# 2019_FDP_SCHEMA.net
KiCad netlist of a schematic drawn in Altium Designer
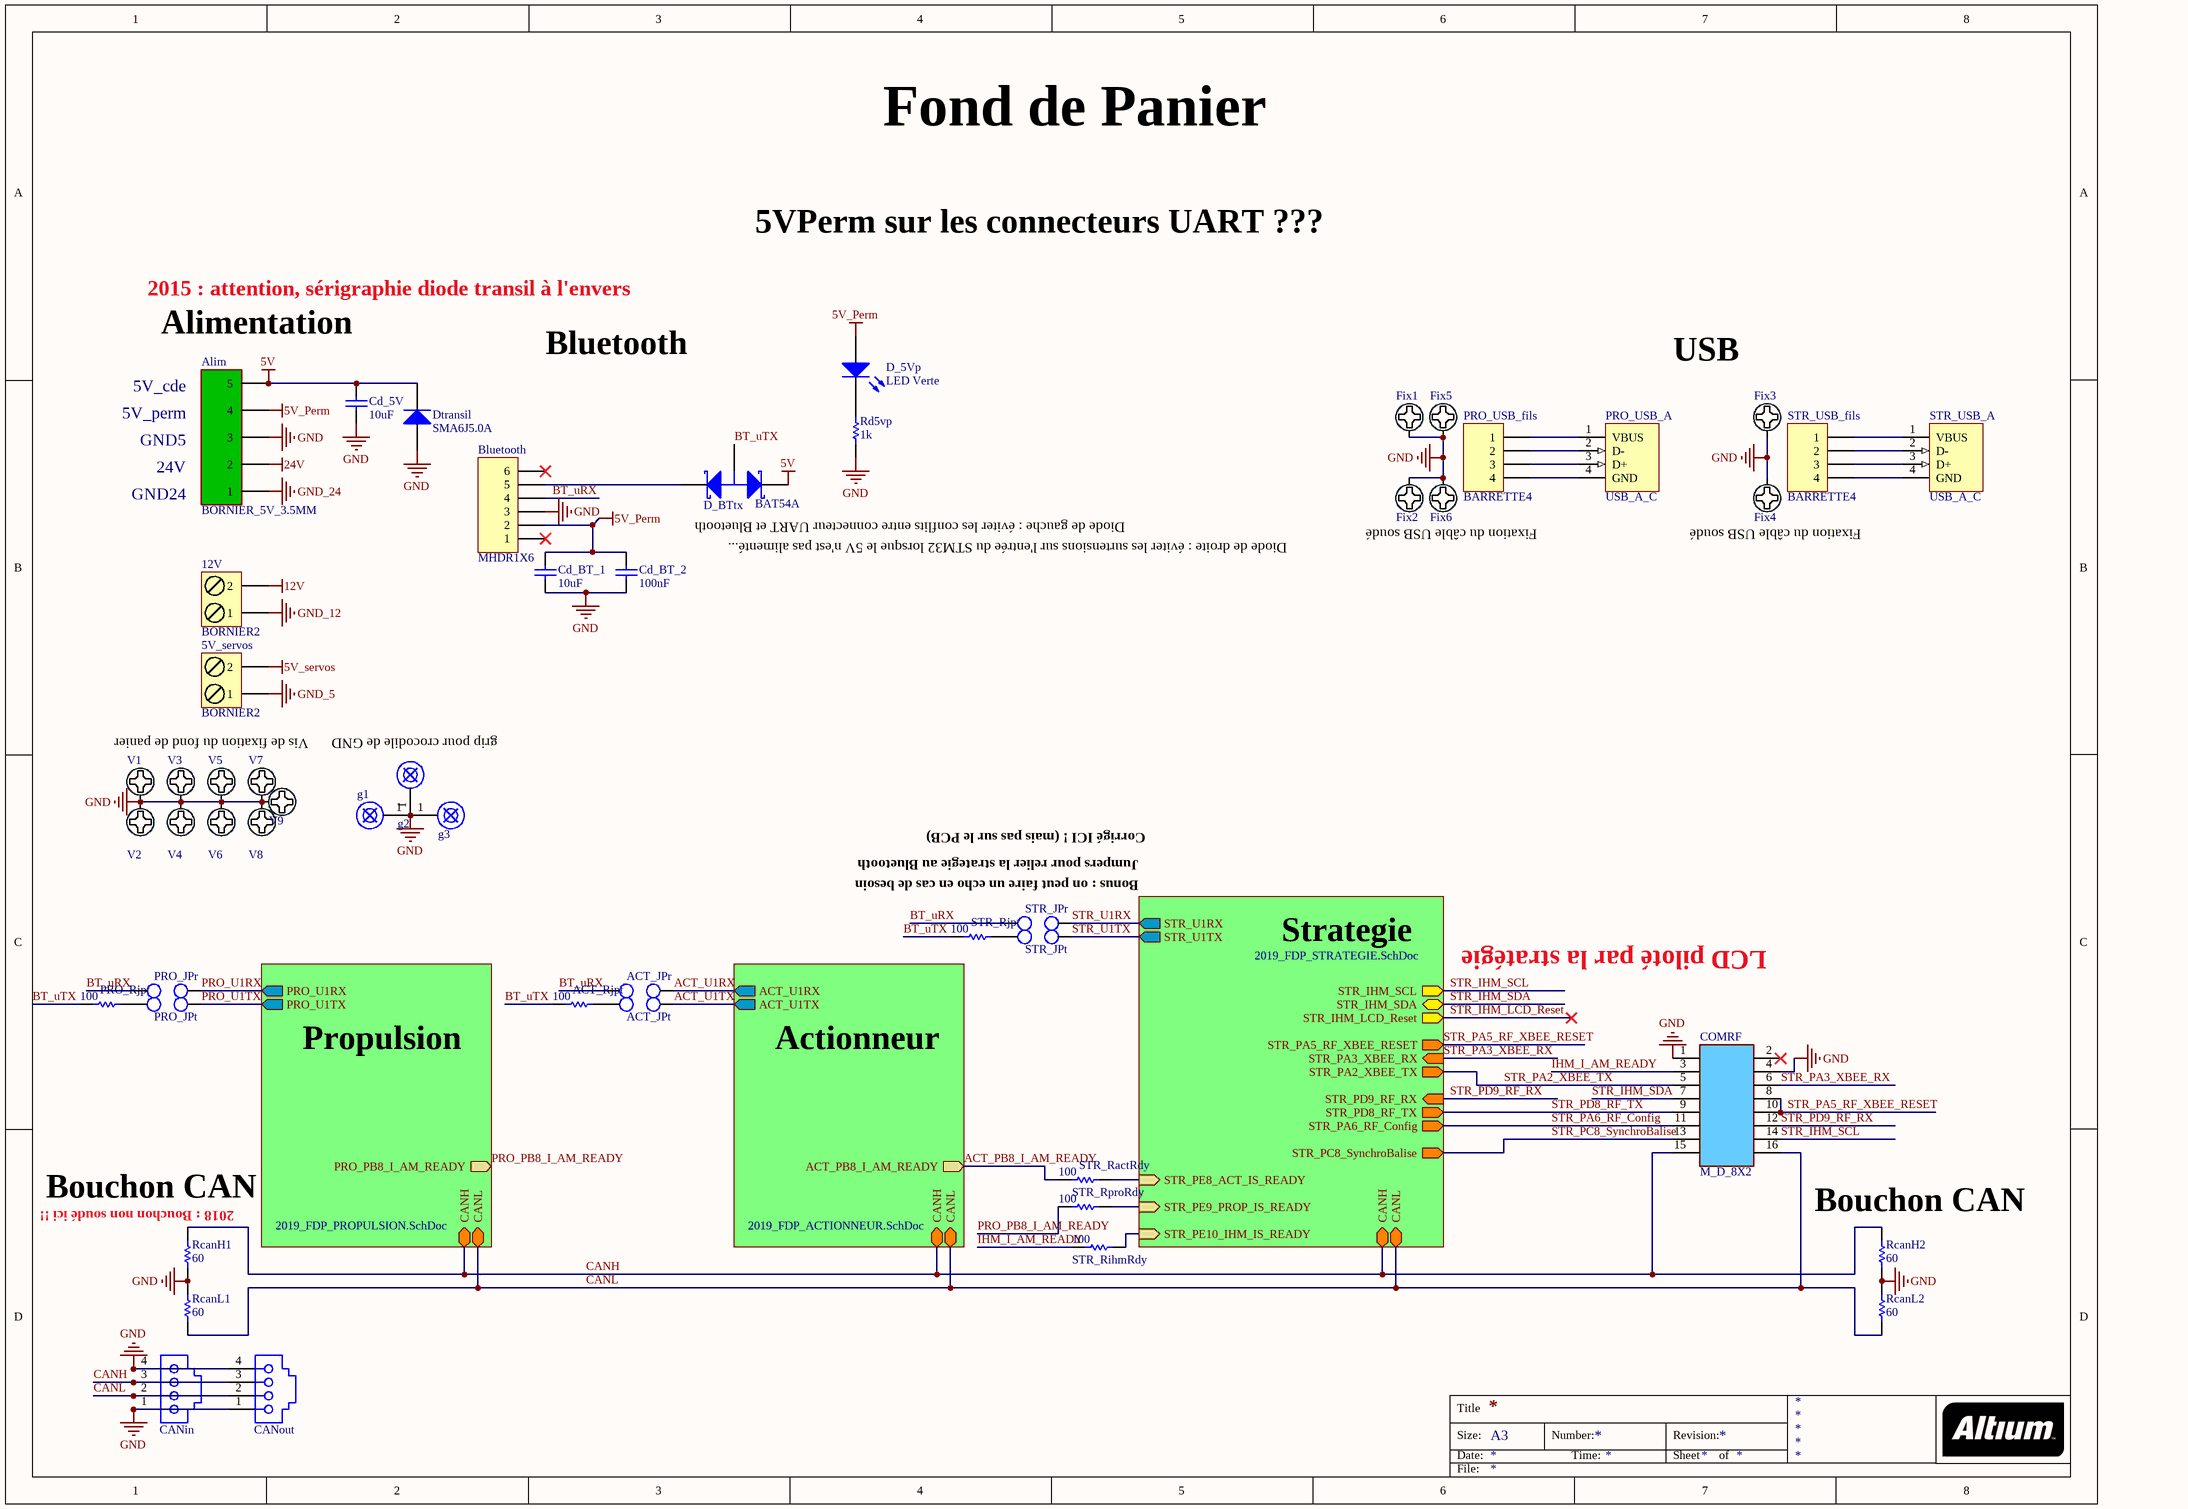
[diagram p0: 2019_FDP_SCHEMA.SchDoc]

(export (version "E")
  (design (tool "Eeschema 10.0.6"))
  (components
    (comp (ref "5V_servos")
      (value "BORNIER2")
      (footprint "BORNIER_2V_5.08MM")
      (description "Terminal blocks, 2 pins, pitch=5mm")
      (libsource (lib "Connecteur") (part "BORNIER2"))
    )
    (comp (ref "12V")
      (value "BORNIER2")
      (footprint "BORNIER_2V_5.08MM")
      (description "Terminal blocks, 2 pins, pitch=5mm")
      (libsource (lib "Connecteur") (part "BORNIER2"))
    )
    (comp (ref "ACT_JPr")
      (value "JUMPER2")
      (footprint "BARRETTE_2_M_D")
      (description "BARRETTE 2 CONTACTS 1 RANGEE MALE DROITE")
      (libsource (lib "connecteurs") (part "JUMPER2"))
    )
    (comp (ref "ACT_JPt")
      (value "JUMPER2")
      (footprint "BARRETTE_2_M_D")
      (description "BARRETTE 2 CONTACTS 1 RANGEE MALE DROITE")
      (libsource (lib "connecteurs") (part "JUMPER2"))
    )
    (comp (ref "ACT_Rjpt")
      (value "100")
      (footprint "R1206_N")
      (description "Resistor")
      (fields (field (name "PUBLISHER") "Altium Limited"))
      (libsource (lib "_ROBOT") (part "Resistor"))
    )
    (comp (ref "Alim")
      (value "BORNIER_5V_3.5MM")
      (footprint "BORNIER_5V_3.5MM_femelle_0")
      (libsource (lib "Connecteur") (part "BORNIER_5V_3.5MM"))
    )
    (comp (ref "Bluetooth")
      (value "MHDR1X6")
      (footprint "HE14_6")
      (description "Header, 6-Pin")
      (fields (field (name "PUBLISHER") "Altium Limited"))
      (libsource (lib "Miscellaneous Connectors") (part "MHDR1X6"))
    )
    (comp (ref "CANin")
      (value "634104149621")
      (footprint "634104149621")
      (description "Modular Jack SMT Vertical Plastic 4P4C Top Entry WR-MJ")
      (fields (field (name "PUBLISHER") "Wurth Elektronik"))
      (libsource (lib "ALTIUM-MJ_VERTICAL_PLASTIC") (part "634104149621"))
    )
    (comp (ref "CANout")
      (value "634104149621")
      (footprint "634104149621")
      (description "Modular Jack SMT Vertical Plastic 4P4C Top Entry WR-MJ")
      (fields (field (name "PUBLISHER") "Wurth Elektronik"))
      (libsource (lib "ALTIUM-MJ_VERTICAL_PLASTIC") (part "634104149621"))
    )
    (comp (ref "Cd_5V")
      (value "10uF")
      (footprint "C1206_N")
      (description "Capacitor")
      (fields (field (name "PUBLISHER") "Altium Limited"))
      (libsource (lib "_ROBOT") (part "Condensateur"))
    )
    (comp (ref "Cd_BT_1")
      (value "10uF")
      (footprint "C1206_N")
      (description "Capacitor")
      (fields (field (name "PUBLISHER") "Altium Limited"))
      (libsource (lib "_ROBOT") (part "Condensateur"))
    )
    (comp (ref "Cd_BT_2")
      (value "100nF")
      (footprint "C0805_N")
      (description "Capacitor")
      (fields (field (name "PUBLISHER") "Altium Limited"))
      (libsource (lib "_ROBOT") (part "Condensateur"))
    )
    (comp (ref "COMRF")
      (value "BARRETTE_8 CONTACTS_2 RANGEES_MALE_DROITE")
      (footprint "HE10/16_M_D_B P")
      (fields (field (name "TYPE") "M_D_8X2"))
      (libsource (lib "connecteurs") (part "BARRETTE_8 CONTACTS_2 RANGEES_MALE_DROITE"))
    )
    (comp (ref "Dtransil")
      (value "SMA6J5.0A")
      (footprint "DO214AC")
      (description "1 Amp General Purpose Rectifier")
      (fields (field (name "PUBLISHER") "Altium Limited"))
      (libsource (lib "Miscellaneous Devices") (part "Diode 1N4001"))
    )
    (comp (ref "D_5Vp")
      (value "LED Verte")
      (footprint "LED_0805")
      (description "Typical LED")
      (fields (field (name "PUBLISHER") "Altium Limited"))
      (libsource (lib "_ROBOT") (part "LED"))
    )
    (comp (ref "D_BTtx")
      (value "BAT54A")
      (footprint "SOT23-3N")
      (description "DIODE SCHOTTKY DOUBLE")
      (fields (field (name "MANUFACTURER") "ZETEX"))
      (libsource (lib "_ROBOT") (part "Diode Shottky double  BAT54A"))
    )
    (comp (ref "Fix1")
      (value "Pad_M3")
      (footprint "Point Test_D3_P1.6mm")
      (description "Vis M3 X 6mm _TORX_Tête 6mm")
      (fields (field (name "PUBLISHER") "Damien Guitton"))
      (libsource (lib "DG_Mecanique") (part "Vis M3 X 6mm _TORX_Tête 6mm"))
    )
    (comp (ref "Fix2")
      (value "Pad_M3")
      (footprint "Point Test_D3_P1.6mm")
      (description "Vis M3 X 6mm _TORX_Tête 6mm")
      (fields (field (name "PUBLISHER") "Damien Guitton"))
      (libsource (lib "DG_Mecanique") (part "Vis M3 X 6mm _TORX_Tête 6mm"))
    )
    (comp (ref "Fix3")
      (value "Pad_M3")
      (footprint "Point Test_D3_P1.6mm")
      (description "Vis M3 X 6mm _TORX_Tête 6mm")
      (fields (field (name "PUBLISHER") "Damien Guitton"))
      (libsource (lib "DG_Mecanique") (part "Vis M3 X 6mm _TORX_Tête 6mm"))
    )
    (comp (ref "Fix4")
      (value "Pad_M3")
      (footprint "Point Test_D3_P1.6mm")
      (description "Vis M3 X 6mm _TORX_Tête 6mm")
      (fields (field (name "PUBLISHER") "Damien Guitton"))
      (libsource (lib "DG_Mecanique") (part "Vis M3 X 6mm _TORX_Tête 6mm"))
    )
    (comp (ref "Fix5")
      (value "Pad_M3")
      (footprint "Point Test_D3_P1.6mm")
      (description "Vis M3 X 6mm _TORX_Tête 6mm")
      (fields (field (name "PUBLISHER") "Damien Guitton"))
      (libsource (lib "DG_Mecanique") (part "Vis M3 X 6mm _TORX_Tête 6mm"))
    )
    (comp (ref "Fix6")
      (value "Pad_M3")
      (footprint "Point Test_D3_P1.6mm")
      (description "Vis M3 X 6mm _TORX_Tête 6mm")
      (fields (field (name "PUBLISHER") "Damien Guitton"))
      (libsource (lib "DG_Mecanique") (part "Vis M3 X 6mm _TORX_Tête 6mm"))
    )
    (comp (ref "g1")
      (value "grip")
      (footprint "POINT_TEST")
      (description "POINT TEST")
      (libsource (lib "connecteurs") (part "POINT_TEST"))
    )
    (comp (ref "g2")
      (value "grip")
      (footprint "POINT_TEST")
      (description "POINT TEST")
      (libsource (lib "connecteurs") (part "POINT_TEST"))
    )
    (comp (ref "g3")
      (value "grip")
      (footprint "POINT_TEST")
      (description "POINT TEST")
      (libsource (lib "connecteurs") (part "POINT_TEST"))
    )
    (comp (ref "PRO_JPr")
      (value "JUMPER2")
      (footprint "BARRETTE_2_M_D")
      (description "BARRETTE 2 CONTACTS 1 RANGEE MALE DROITE")
      (libsource (lib "connecteurs") (part "JUMPER2"))
    )
    (comp (ref "PRO_JPt")
      (value "JUMPER2")
      (footprint "BARRETTE_2_M_D")
      (description "BARRETTE 2 CONTACTS 1 RANGEE MALE DROITE")
      (libsource (lib "connecteurs") (part "JUMPER2"))
    )
    (comp (ref "PRO_Rjpt")
      (value "100")
      (footprint "R1206_N")
      (description "Resistor")
      (fields (field (name "PUBLISHER") "Altium Limited"))
      (libsource (lib "_ROBOT") (part "Resistor"))
    )
    (comp (ref "PRO_USB_A")
      (value "USB_A_COUDEE")
      (footprint "USB_A_C")
      (description "EMBASE USB TRAVERSANTE TYPE A COUDEE")
      (fields (field (name "TYPE") "USB_A_C"))
      (libsource (lib "connecteurs") (part "USB_A_COUDEE"))
    )
    (comp (ref "PRO_USB_fils")
      (value "BARRETTE4")
      (footprint "HE14_4")
      (description "Header, 4-Pin")
      (fields (field (name "PUBLISHER") "Altium Limited"))
      (libsource (lib "Connecteur") (part "BARRETTE4"))
    )
    (comp (ref "RcanH1")
      (value "60")
      (footprint "R1206_N")
      (description "Resistor")
      (fields (field (name "PUBLISHER") "Altium Limited"))
      (libsource (lib "_ROBOT") (part "Resistor"))
    )
    (comp (ref "RcanH2")
      (value "60")
      (footprint "R1206_N")
      (description "Resistor")
      (fields (field (name "PUBLISHER") "Altium Limited"))
      (libsource (lib "_ROBOT") (part "Resistor"))
    )
    (comp (ref "RcanL1")
      (value "60")
      (footprint "R1206_N")
      (description "Resistor")
      (fields (field (name "PUBLISHER") "Altium Limited"))
      (libsource (lib "_ROBOT") (part "Resistor"))
    )
    (comp (ref "RcanL2")
      (value "60")
      (footprint "R1206_N")
      (description "Resistor")
      (fields (field (name "PUBLISHER") "Altium Limited"))
      (libsource (lib "_ROBOT") (part "Resistor"))
    )
    (comp (ref "Rd5vp")
      (value "1k")
      (footprint "R1206_N")
      (description "Resistor")
      (fields (field (name "PUBLISHER") "Altium Limited"))
      (libsource (lib "_ROBOT") (part "Resistor"))
    )
    (comp (ref "STR_JPr")
      (value "JUMPER2")
      (footprint "BARRETTE_2_M_D")
      (description "BARRETTE 2 CONTACTS 1 RANGEE MALE DROITE")
      (libsource (lib "connecteurs") (part "JUMPER2"))
    )
    (comp (ref "STR_JPt")
      (value "JUMPER2")
      (footprint "BARRETTE_2_M_D")
      (description "BARRETTE 2 CONTACTS 1 RANGEE MALE DROITE")
      (libsource (lib "connecteurs") (part "JUMPER2"))
    )
    (comp (ref "STR_RactRdy")
      (value "100")
      (footprint "R1206_N")
      (description "Resistor")
      (fields (field (name "PUBLISHER") "Altium Limited"))
      (libsource (lib "_ROBOT") (part "Resistor"))
    )
    (comp (ref "STR_RihmRdy")
      (value "100")
      (footprint "R1206_N")
      (description "Resistor")
      (fields (field (name "PUBLISHER") "Altium Limited"))
      (libsource (lib "_ROBOT") (part "Resistor"))
    )
    (comp (ref "STR_Rjpt")
      (value "100")
      (footprint "R1206_N")
      (description "Resistor")
      (fields (field (name "PUBLISHER") "Altium Limited"))
      (libsource (lib "_ROBOT") (part "Resistor"))
    )
    (comp (ref "STR_RproRdy")
      (value "100")
      (footprint "R1206_N")
      (description "Resistor")
      (fields (field (name "PUBLISHER") "Altium Limited"))
      (libsource (lib "_ROBOT") (part "Resistor"))
    )
    (comp (ref "STR_USB_A")
      (value "USB_A_COUDEE")
      (footprint "USB_A_C")
      (description "EMBASE USB TRAVERSANTE TYPE A COUDEE")
      (fields (field (name "TYPE") "USB_A_C"))
      (libsource (lib "connecteurs") (part "USB_A_COUDEE"))
    )
    (comp (ref "STR_USB_fils")
      (value "BARRETTE4")
      (footprint "HE14_4")
      (description "Header, 4-Pin")
      (fields (field (name "PUBLISHER") "Altium Limited"))
      (libsource (lib "Connecteur") (part "BARRETTE4"))
    )
    (comp (ref "V1")
      (value "Pad_M3")
      (footprint "M3x6mm Torx")
      (description "Vis M3 X 6mm _TORX_Tête 6mm")
      (fields (field (name "PUBLISHER") "Damien Guitton"))
      (libsource (lib "DG_Mecanique") (part "Vis M3 X 6mm _TORX_Tête 6mm"))
    )
    (comp (ref "V2")
      (value "Pad_M3")
      (footprint "M3x6mm Torx")
      (description "Vis M3 X 6mm _TORX_Tête 6mm")
      (fields (field (name "PUBLISHER") "Damien Guitton"))
      (libsource (lib "DG_Mecanique") (part "Vis M3 X 6mm _TORX_Tête 6mm"))
    )
    (comp (ref "V3")
      (value "Pad_M3")
      (footprint "M3x6mm Torx")
      (description "Vis M3 X 6mm _TORX_Tête 6mm")
      (fields (field (name "PUBLISHER") "Damien Guitton"))
      (libsource (lib "DG_Mecanique") (part "Vis M3 X 6mm _TORX_Tête 6mm"))
    )
    (comp (ref "V4")
      (value "Pad_M3")
      (footprint "M3x6mm Torx")
      (description "Vis M3 X 6mm _TORX_Tête 6mm")
      (fields (field (name "PUBLISHER") "Damien Guitton"))
      (libsource (lib "DG_Mecanique") (part "Vis M3 X 6mm _TORX_Tête 6mm"))
    )
    (comp (ref "V5")
      (value "Pad_M3")
      (footprint "M3x6mm Torx")
      (description "Vis M3 X 6mm _TORX_Tête 6mm")
      (fields (field (name "PUBLISHER") "Damien Guitton"))
      (libsource (lib "DG_Mecanique") (part "Vis M3 X 6mm _TORX_Tête 6mm"))
    )
    (comp (ref "V6")
      (value "Pad_M3")
      (footprint "M3x6mm Torx")
      (description "Vis M3 X 6mm _TORX_Tête 6mm")
      (fields (field (name "PUBLISHER") "Damien Guitton"))
      (libsource (lib "DG_Mecanique") (part "Vis M3 X 6mm _TORX_Tête 6mm"))
    )
    (comp (ref "V7")
      (value "Pad_M3")
      (footprint "M3x6mm Torx")
      (description "Vis M3 X 6mm _TORX_Tête 6mm")
      (fields (field (name "PUBLISHER") "Damien Guitton"))
      (libsource (lib "DG_Mecanique") (part "Vis M3 X 6mm _TORX_Tête 6mm"))
    )
    (comp (ref "V8")
      (value "Pad_M3")
      (footprint "M3x6mm Torx")
      (description "Vis M3 X 6mm _TORX_Tête 6mm")
      (fields (field (name "PUBLISHER") "Damien Guitton"))
      (libsource (lib "DG_Mecanique") (part "Vis M3 X 6mm _TORX_Tête 6mm"))
    )
    (comp (ref "V9")
      (value "Pad_M3")
      (footprint "M3x6mm Torx")
      (description "Vis M3 X 6mm _TORX_Tête 6mm")
      (fields (field (name "PUBLISHER") "Damien Guitton"))
      (libsource (lib "DG_Mecanique") (part "Vis M3 X 6mm _TORX_Tête 6mm"))
    )
  )
  (nets
    (net (code "1") (name "/ACT_PB8_I_AM_READY") (class "Default")
      (node (ref "STR_RactRdy") (pin "2") (pinfunction "2_2") (pintype "passive"))
    )
    (net (code "2") (name "/ACT_U1RX") (class "Default")
      (node (ref "ACT_JPr") (pin "2") (pinfunction "2_2") (pintype "passive"))
    )
    (net (code "3") (name "/ACT_U1TX") (class "Default")
      (node (ref "ACT_JPt") (pin "2") (pinfunction "2_2") (pintype "passive"))
    )
    (net (code "4") (name "/BT_uRX") (class "Default")
      (node (ref "ACT_JPr") (pin "1") (pinfunction "1_1") (pintype "passive"))
      (node (ref "Bluetooth") (pin "4") (pinfunction "4_4") (pintype "passive"))
      (node (ref "PRO_JPr") (pin "1") (pinfunction "1_1") (pintype "passive"))
      (node (ref "STR_JPr") (pin "1") (pinfunction "1_1") (pintype "passive"))
    )
    (net (code "5") (name "/BT_uTX") (class "Default")
      (node (ref "ACT_Rjpt") (pin "2") (pinfunction "2_2") (pintype "passive"))
      (node (ref "D_BTtx") (pin "3") (pinfunction "A_3") (pintype "passive"))
      (node (ref "PRO_Rjpt") (pin "2") (pinfunction "2_2") (pintype "passive"))
      (node (ref "STR_Rjpt") (pin "2") (pinfunction "2_2") (pintype "passive"))
    )
    (net (code "6") (name "/CANH") (class "Default")
      (node (ref "CANin") (pin "3") (pinfunction "3_3") (pintype "passive"))
      (node (ref "CANout") (pin "3") (pinfunction "3_3") (pintype "passive"))
      (node (ref "COMRF") (pin "15") (pinfunction "15_15") (pintype "passive"))
      (node (ref "RcanH1") (pin "2") (pinfunction "2_2") (pintype "passive"))
      (node (ref "RcanH2") (pin "1") (pinfunction "1_1") (pintype "passive"))
    )
    (net (code "7") (name "/CANL") (class "Default")
      (node (ref "CANin") (pin "2") (pinfunction "2_2") (pintype "passive"))
      (node (ref "CANout") (pin "2") (pinfunction "2_2") (pintype "passive"))
      (node (ref "COMRF") (pin "16") (pinfunction "16_16") (pintype "passive"))
      (node (ref "RcanL1") (pin "1") (pinfunction "1_1") (pintype "passive"))
      (node (ref "RcanL2") (pin "1") (pinfunction "1_1") (pintype "passive"))
    )
    (net (code "8") (name "/IHM_I_AM_READY") (class "Default")
      (node (ref "COMRF") (pin "3") (pinfunction "3_3") (pintype "passive"))
      (node (ref "STR_RihmRdy") (pin "2") (pinfunction "2_2") (pintype "passive"))
    )
    (net (code "9") (name "/PRO_PB8_I_AM_READY") (class "Default")
      (node (ref "STR_RproRdy") (pin "2") (pinfunction "2_2") (pintype "passive"))
    )
    (net (code "10") (name "/PRO_U1RX") (class "Default")
      (node (ref "PRO_JPr") (pin "2") (pinfunction "2_2") (pintype "passive"))
    )
    (net (code "11") (name "/PRO_U1TX") (class "Default")
      (node (ref "PRO_JPt") (pin "2") (pinfunction "2_2") (pintype "passive"))
    )
    (net (code "13") (name "/STR_IHM_SCL") (class "Default")
      (node (ref "COMRF") (pin "14") (pinfunction "14_14") (pintype "passive"))
    )
    (net (code "14") (name "/STR_IHM_SDA") (class "Default")
      (node (ref "COMRF") (pin "7") (pinfunction "7_7") (pintype "passive"))
    )
    (net (code "15") (name "/STR_PA2_XBEE_TX") (class "Default")
      (node (ref "COMRF") (pin "5") (pinfunction "5_5") (pintype "passive"))
    )
    (net (code "16") (name "/STR_PA3_XBEE_RX") (class "Default")
      (node (ref "COMRF") (pin "6") (pinfunction "6_6") (pintype "passive"))
    )
    (net (code "17") (name "/STR_PA5_RF_XBEE_RESET") (class "Default")
      (node (ref "COMRF") (pin "10") (pinfunction "10_10") (pintype "passive"))
      (node (ref "COMRF") (pin "8") (pinfunction "8_8") (pintype "passive"))
    )
    (net (code "18") (name "/STR_PA6_RF_Config") (class "Default")
      (node (ref "COMRF") (pin "11") (pinfunction "11_11") (pintype "passive"))
    )
    (net (code "19") (name "/STR_PC8_SynchroBalise") (class "Default")
      (node (ref "COMRF") (pin "13") (pinfunction "13_13") (pintype "passive"))
    )
    (net (code "20") (name "/STR_PD8_RF_TX") (class "Default")
      (node (ref "COMRF") (pin "9") (pinfunction "9_9") (pintype "passive"))
    )
    (net (code "21") (name "/STR_PD9_RF_RX") (class "Default")
      (node (ref "COMRF") (pin "12") (pinfunction "12_12") (pintype "passive"))
    )
    (net (code "22") (name "/STR_PE8_ACT_IS_READY") (class "Default")
      (node (ref "STR_RactRdy") (pin "1") (pinfunction "1_1") (pintype "passive"))
    )
    (net (code "23") (name "/STR_PE9_PROP_IS_READY") (class "Default")
      (node (ref "STR_RproRdy") (pin "1") (pinfunction "1_1") (pintype "passive"))
    )
    (net (code "24") (name "/STR_PE10_IHM_IS_READY") (class "Default")
      (node (ref "STR_RihmRdy") (pin "1") (pinfunction "1_1") (pintype "passive"))
    )
    (net (code "25") (name "/STR_U1RX") (class "Default")
      (node (ref "STR_JPr") (pin "2") (pinfunction "2_2") (pintype "passive"))
    )
    (net (code "26") (name "/STR_U1TX") (class "Default")
      (node (ref "STR_JPt") (pin "2") (pinfunction "2_2") (pintype "passive"))
    )
    (net (code "27") (name "5V") (class "Default")
      (node (ref "Alim") (pin "5") (pinfunction "5_5") (pintype "passive"))
      (node (ref "Cd_5V") (pin "2") (pinfunction "2_2") (pintype "passive"))
      (node (ref "D_BTtx") (pin "2") (pinfunction "K2_2") (pintype "passive"))
      (node (ref "Dtransil") (pin "2") (pinfunction "K_2") (pintype "passive"))
    )
    (net (code "28") (name "5V_Perm") (class "Default")
      (node (ref "Alim") (pin "4") (pinfunction "4_4") (pintype "passive"))
      (node (ref "Bluetooth") (pin "2") (pinfunction "2_2") (pintype "passive"))
      (node (ref "Cd_BT_1") (pin "2") (pinfunction "2_2") (pintype "passive"))
      (node (ref "Cd_BT_2") (pin "2") (pinfunction "2_2") (pintype "passive"))
      (node (ref "D_5Vp") (pin "1") (pinfunction "A_1") (pintype "passive"))
    )
    (net (code "29") (name "5V_servos") (class "Default")
      (node (ref "5V_servos") (pin "2") (pinfunction "2_2") (pintype "passive"))
    )
    (net (code "30") (name "12V") (class "Default")
      (node (ref "12V") (pin "2") (pinfunction "2_2") (pintype "passive"))
    )
    (net (code "31") (name "24V") (class "Default")
      (node (ref "Alim") (pin "2") (pinfunction "2_2") (pintype "passive"))
    )
    (net (code "32") (name "GND") (class "Default")
      (node (ref "Alim") (pin "3") (pinfunction "3_3") (pintype "passive"))
      (node (ref "Bluetooth") (pin "3") (pinfunction "3_3") (pintype "passive"))
      (node (ref "CANin") (pin "1") (pinfunction "1_1") (pintype "passive"))
      (node (ref "CANin") (pin "4") (pinfunction "4_4") (pintype "passive"))
      (node (ref "CANout") (pin "1") (pinfunction "1_1") (pintype "passive"))
      (node (ref "CANout") (pin "4") (pinfunction "4_4") (pintype "passive"))
      (node (ref "COMRF") (pin "1") (pinfunction "1_1") (pintype "passive"))
      (node (ref "COMRF") (pin "4") (pinfunction "4_4") (pintype "passive"))
      (node (ref "Cd_5V") (pin "1") (pinfunction "1_1") (pintype "passive"))
      (node (ref "Cd_BT_1") (pin "1") (pinfunction "1_1") (pintype "passive"))
      (node (ref "Cd_BT_2") (pin "1") (pinfunction "1_1") (pintype "passive"))
      (node (ref "Dtransil") (pin "1") (pinfunction "A_1") (pintype "passive"))
      (node (ref "Fix1") (pin "1") (pinfunction "1_1") (pintype "passive"))
      (node (ref "Fix2") (pin "1") (pinfunction "1_1") (pintype "passive"))
      (node (ref "Fix3") (pin "1") (pinfunction "1_1") (pintype "passive"))
      (node (ref "Fix4") (pin "1") (pinfunction "1_1") (pintype "passive"))
      (node (ref "Fix5") (pin "1") (pinfunction "1_1") (pintype "passive"))
      (node (ref "Fix6") (pin "1") (pinfunction "1_1") (pintype "passive"))
      (node (ref "RcanH1") (pin "1") (pinfunction "1_1") (pintype "passive"))
      (node (ref "RcanH2") (pin "2") (pinfunction "2_2") (pintype "passive"))
      (node (ref "RcanL1") (pin "2") (pinfunction "2_2") (pintype "passive"))
      (node (ref "RcanL2") (pin "2") (pinfunction "2_2") (pintype "passive"))
      (node (ref "Rd5vp") (pin "2") (pinfunction "2_2") (pintype "passive"))
      (node (ref "V1") (pin "1") (pinfunction "1_1") (pintype "passive"))
      (node (ref "V2") (pin "1") (pinfunction "1_1") (pintype "passive"))
      (node (ref "V3") (pin "1") (pinfunction "1_1") (pintype "passive"))
      (node (ref "V4") (pin "1") (pinfunction "1_1") (pintype "passive"))
      (node (ref "V5") (pin "1") (pinfunction "1_1") (pintype "passive"))
      (node (ref "V6") (pin "1") (pinfunction "1_1") (pintype "passive"))
      (node (ref "V7") (pin "1") (pinfunction "1_1") (pintype "passive"))
      (node (ref "V8") (pin "1") (pinfunction "1_1") (pintype "passive"))
      (node (ref "V9") (pin "1") (pinfunction "1_1") (pintype "passive"))
      (node (ref "g1") (pin "1") (pinfunction "3_1") (pintype "passive"))
      (node (ref "g2") (pin "1") (pinfunction "3_1") (pintype "passive"))
      (node (ref "g3") (pin "1") (pinfunction "3_1") (pintype "passive"))
    )
    (net (code "33") (name "GND_5") (class "Default")
      (node (ref "5V_servos") (pin "1") (pinfunction "1_1") (pintype "passive"))
    )
    (net (code "34") (name "GND_12") (class "Default")
      (node (ref "12V") (pin "1") (pinfunction "1_1") (pintype "passive"))
    )
    (net (code "35") (name "GND_24") (class "Default")
      (node (ref "Alim") (pin "1") (pinfunction "1_1") (pintype "passive"))
    )
    (net (code "36") (name "Net-(ACT_JPt-Pad1)") (class "Default")
      (node (ref "ACT_JPt") (pin "1") (pinfunction "1_1") (pintype "passive"))
      (node (ref "ACT_Rjpt") (pin "1") (pinfunction "1_1") (pintype "passive"))
    )
    (net (code "37") (name "Net-(D_5Vp-K)") (class "Default")
      (node (ref "D_5Vp") (pin "2") (pinfunction "K_2") (pintype "passive"))
      (node (ref "Rd5vp") (pin "1") (pinfunction "1_1") (pintype "passive"))
    )
    (net (code "38") (name "Net-(D_BTtx-K1)") (class "Default")
      (node (ref "Bluetooth") (pin "5") (pinfunction "5_5") (pintype "passive"))
      (node (ref "D_BTtx") (pin "1") (pinfunction "K1_1") (pintype "passive"))
    )
    (net (code "39") (name "Net-(PRO_JPt-Pad1)") (class "Default")
      (node (ref "PRO_JPt") (pin "1") (pinfunction "1_1") (pintype "passive"))
      (node (ref "PRO_Rjpt") (pin "1") (pinfunction "1_1") (pintype "passive"))
    )
    (net (code "40") (name "Net-(PRO_USB_A-D+)") (class "Default")
      (node (ref "PRO_USB_A") (pin "3") (pinfunction "D+_3") (pintype "input"))
      (node (ref "PRO_USB_fils") (pin "3") (pinfunction "3_3") (pintype "passive"))
    )
    (net (code "41") (name "Net-(PRO_USB_A-D-)") (class "Default")
      (node (ref "PRO_USB_A") (pin "2") (pinfunction "D-_2") (pintype "input"))
      (node (ref "PRO_USB_fils") (pin "2") (pinfunction "2_2") (pintype "passive"))
    )
    (net (code "42") (name "Net-(PRO_USB_A-GND)") (class "Default")
      (node (ref "PRO_USB_A") (pin "4") (pinfunction "GND_4") (pintype "power_in"))
      (node (ref "PRO_USB_fils") (pin "4") (pinfunction "4_4") (pintype "passive"))
    )
    (net (code "43") (name "Net-(PRO_USB_A-VBUS)") (class "Default")
      (node (ref "PRO_USB_A") (pin "1") (pinfunction "VBUS_1") (pintype "power_in"))
      (node (ref "PRO_USB_fils") (pin "1") (pinfunction "1_1") (pintype "passive"))
    )
    (net (code "44") (name "Net-(STR_JPt-Pad1)") (class "Default")
      (node (ref "STR_JPt") (pin "1") (pinfunction "1_1") (pintype "passive"))
      (node (ref "STR_Rjpt") (pin "1") (pinfunction "1_1") (pintype "passive"))
    )
    (net (code "45") (name "Net-(STR_USB_A-D+)") (class "Default")
      (node (ref "STR_USB_A") (pin "3") (pinfunction "D+_3") (pintype "input"))
      (node (ref "STR_USB_fils") (pin "3") (pinfunction "3_3") (pintype "passive"))
    )
    (net (code "46") (name "Net-(STR_USB_A-D-)") (class "Default")
      (node (ref "STR_USB_A") (pin "2") (pinfunction "D-_2") (pintype "input"))
      (node (ref "STR_USB_fils") (pin "2") (pinfunction "2_2") (pintype "passive"))
    )
    (net (code "47") (name "Net-(STR_USB_A-GND)") (class "Default")
      (node (ref "STR_USB_A") (pin "4") (pinfunction "GND_4") (pintype "power_in"))
      (node (ref "STR_USB_fils") (pin "4") (pinfunction "4_4") (pintype "passive"))
    )
    (net (code "48") (name "Net-(STR_USB_A-VBUS)") (class "Default")
      (node (ref "STR_USB_A") (pin "1") (pinfunction "VBUS_1") (pintype "power_in"))
      (node (ref "STR_USB_fils") (pin "1") (pinfunction "1_1") (pintype "passive"))
    )
    (net (code "49") (name "unconnected-(Bluetooth-Pad1)") (class "Default")
      (node (ref "Bluetooth") (pin "1") (pinfunction "1_1") (pintype "passive+no_connect"))
    )
    (net (code "50") (name "unconnected-(Bluetooth-Pad6)") (class "Default")
      (node (ref "Bluetooth") (pin "6") (pinfunction "6_6") (pintype "passive+no_connect"))
    )
    (net (code "51") (name "unconnected-(COMRF-Pad2)") (class "Default")
      (node (ref "COMRF") (pin "2") (pinfunction "2_2") (pintype "passive+no_connect"))
    )
  )
)
